# PWR_PROT.net
KiCad netlist of a schematic drawn in Altium Designer
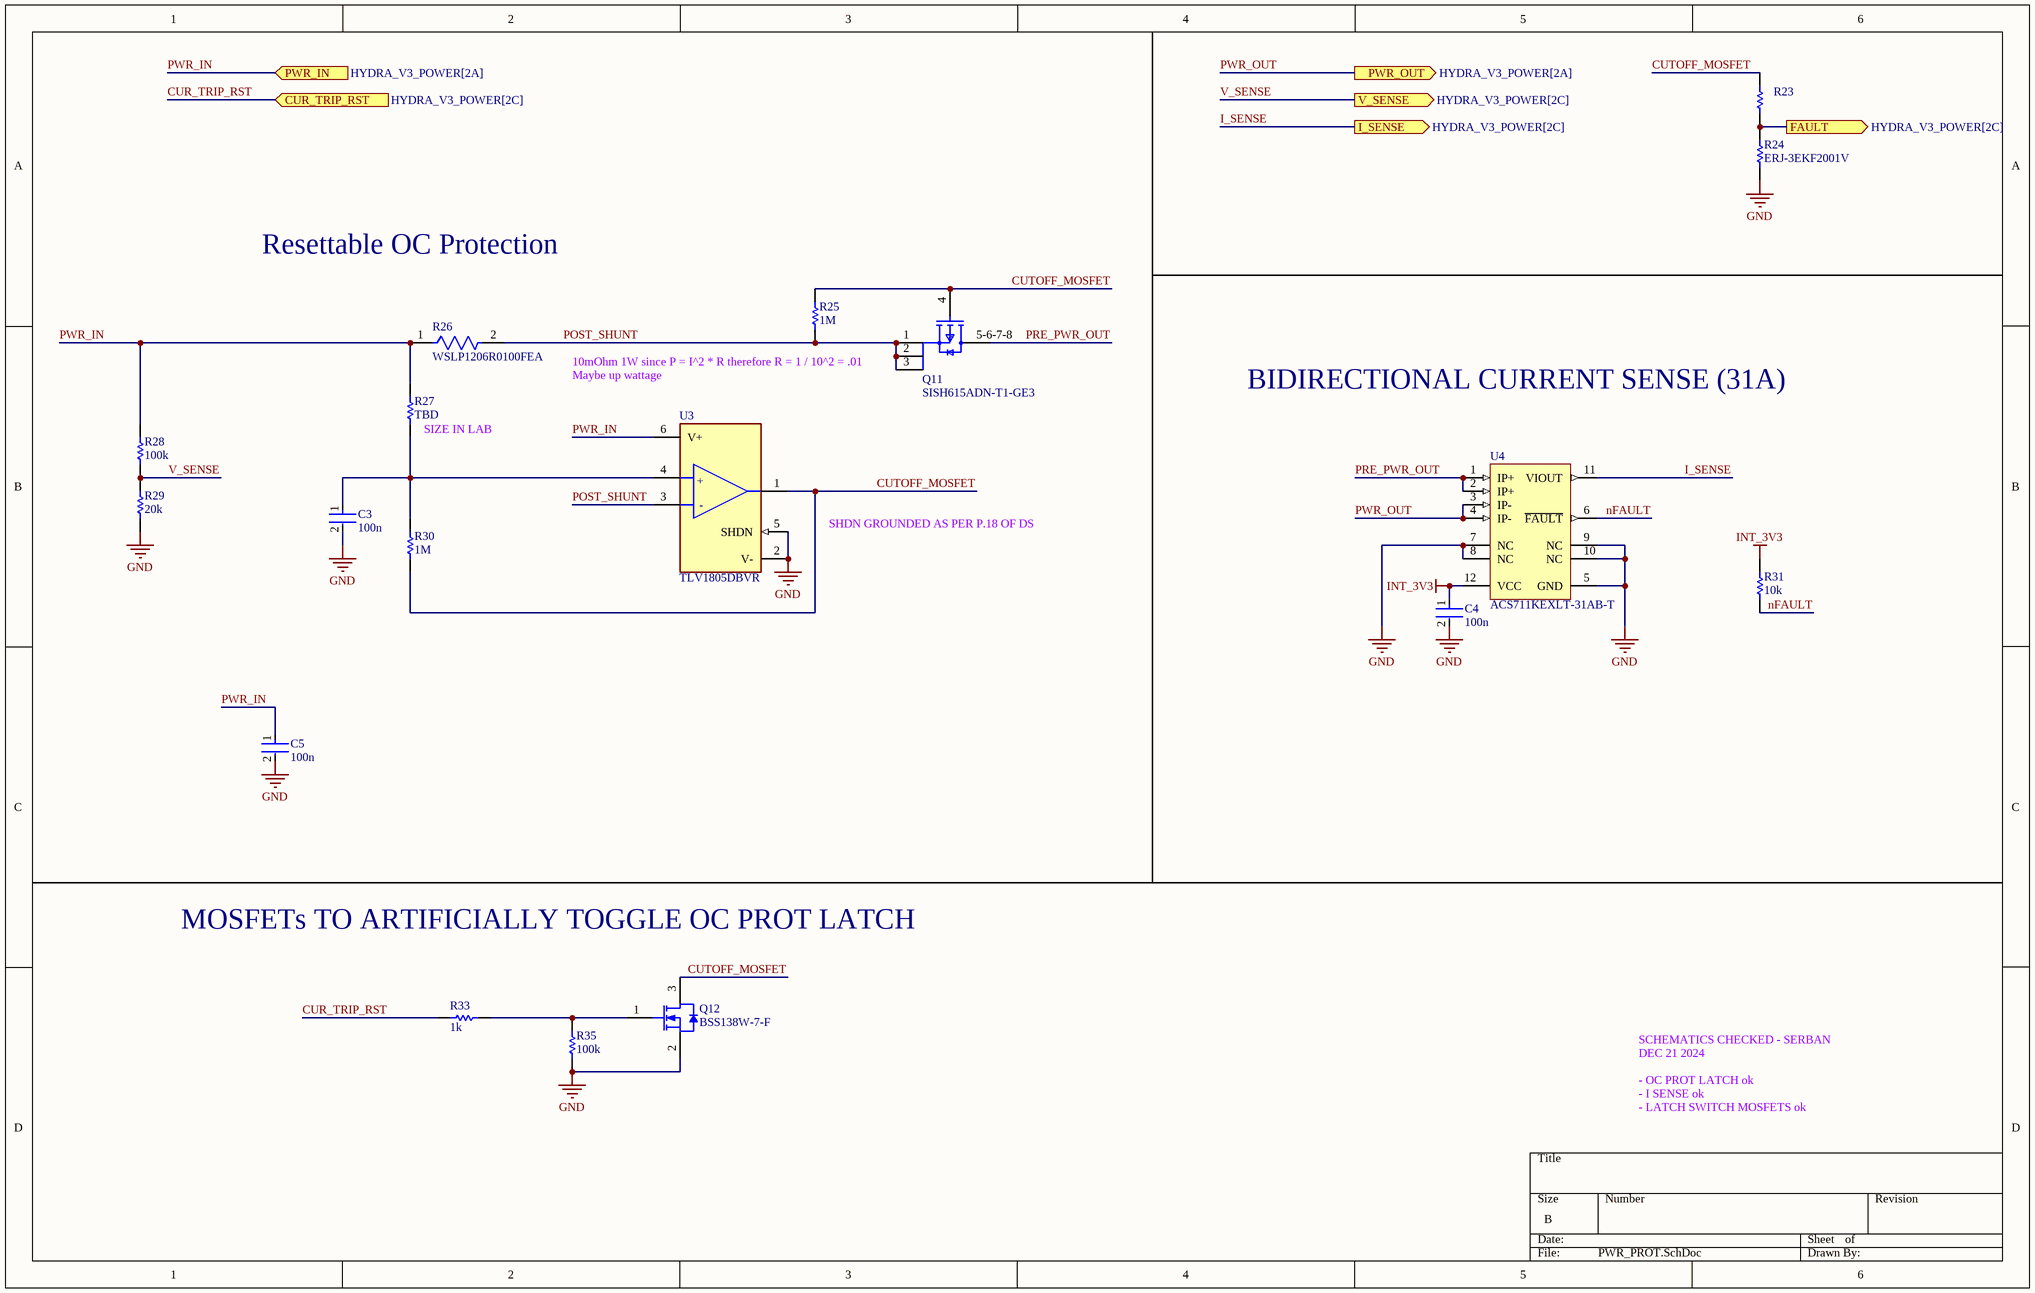
[diagram p0: PWR_PROT.SchDoc]

(export (version "E")
  (design (tool "Eeschema 10.0.6"))
  (components
    (comp (ref "C3")
      (value "100n")
      (footprint "FP-0402-L_1_0_0_05-W_0_5-IPC_A")
      (description "LARGE PADS, 0402 CAP, CHANGE COMMENT TO MATCH REAL P/N")
      (libsource (lib "Space Concordia") (part "b4654b650e69147ec39a6b967a45e02"))
    )
    (comp (ref "C4")
      (value "100n")
      (footprint "FP-0402-L_1_0_0_05-W_0_5-IPC_A")
      (description "LARGE PADS, 0402 CAP, CHANGE COMMENT TO MATCH REAL P/N")
      (libsource (lib "Space Concordia") (part "b4654b650e69147ec39a6b967a45e02"))
    )
    (comp (ref "C5")
      (value "100n")
      (footprint "FP-0402-L_1_0_0_05-W_0_5-IPC_A")
      (description "LARGE PADS, 0402 CAP, CHANGE COMMENT TO MATCH REAL P/N")
      (libsource (lib "Space Concordia") (part "b4654b650e69147ec39a6b967a45e02"))
    )
    (comp (ref "Q11")
      (value "SISH615ADN-T1-GE3")
      (footprint "SISH615ADN-T1-GE3-Footprint-1")
      (description "Trans MOSFET P-CH 20V 22.1A 8-Pin PowerPAK 1212 EP T/R")
      (libsource (lib "Space Concordia") (part "CMP-013-00036-4"))
    )
    (comp (ref "Q12")
      (value "BSS138W-7-F")
      (footprint "DIOD-SOT323-3_V")
      (fields (field (name "MANUFACTURER") "DiodesIncorporated"))
      (libsource (lib "Altium Content Vault") (part "NEMOS-GSD-3"))
    )
    (comp (ref "R23")
      (value "ERJ3EKF1002V")
      (footprint "RESC1609X55X30LL15T15")
      (description "Chip Resistor, 10 KOhm, +/- 1%, 0.1 W, -55 to 155 degC, 0603 (1608 Metric), RoHS, Tape and Reel")
      (fields (field (name "TOLERANCE") "1%") (field (name "MANUFACTURER") "Panasonic"))
      (libsource (lib "Altium Content Vault") (part "RES-2"))
    )
    (comp (ref "R24")
      (value "ERJ-3EKF2001V")
      (footprint "RESC1608X55X30ML15T15")
      (fields (field (name "MANUFACTURER") "Panasonic"))
      (libsource (lib "Altium Content Vault") (part "RES"))
    )
    (comp (ref "R25")
      (value "1M")
      (footprint "R0603B")
      (description "Resistor")
      (libsource (lib "Space Concordia") (part "Resistor"))
    )
    (comp (ref "R26")
      (value "WSLP1206R0100FEA")
      (footprint "FP-WSLP1206-FP_1_65x1_93x-MFG")
      (description "RES 0.01 OHM 1% 1W 1206")
      (fields (field (name "TOLERANCE") "1%"))
      (libsource (lib "Altium Content Vault") (part "1029c3af85768c4190bb7ad29bc67b5"))
    )
    (comp (ref "R27")
      (value "TBD")
      (footprint "R0603B")
      (description "Resistor")
      (libsource (lib "Space Concordia") (part "Resistor"))
    )
    (comp (ref "R28")
      (value "100k")
      (footprint "R0603B")
      (description "Resistor")
      (libsource (lib "Space Concordia") (part "Resistor"))
    )
    (comp (ref "R29")
      (value "20k")
      (footprint "R0603B")
      (description "Resistor")
      (libsource (lib "Space Concordia") (part "Resistor"))
    )
    (comp (ref "R30")
      (value "1M")
      (footprint "R0603B")
      (description "Resistor")
      (libsource (lib "Space Concordia") (part "Resistor"))
    )
    (comp (ref "R31")
      (value "10k")
      (footprint "R0603B")
      (description "Resistor")
      (libsource (lib "Space Concordia") (part "Resistor"))
    )
    (comp (ref "R33")
      (value "1k")
      (footprint "R0603B")
      (description "Resistor")
      (libsource (lib "Space Concordia") (part "Resistor"))
    )
    (comp (ref "R35")
      (value "100k")
      (footprint "R0603B")
      (description "Resistor")
      (libsource (lib "Space Concordia") (part "Resistor"))
    )
    (comp (ref "U3")
      (value "TLV1805DBVR")
      (footprint "FP-DBV0006A-IPC_C")
      (description "40V, RAIL-TO-RAIL INPUT, PUSH-PU")
      (libsource (lib "Altium Content Vault") (part "c7aa3bc3dbf0dc8b0b0354779bd1228"))
    )
    (comp (ref "U4")
      (value "ACS711KEXLT-31AB-T")
      (footprint "ALEG-EX-12_V")
      (libsource (lib "Altium Content Vault") (part "ALEG-ACS711-QFN-12"))
    )
  )
  (nets
    (net (code "1") (name "/CUR_TRIP_RST") (class "Default")
      (node (ref "R33") (pin "2") (pinfunction "2_2") (pintype "passive"))
    )
    (net (code "2") (name "/CUTOFF_MOSFET") (class "Default")
      (node (ref "Q11") (pin "4") (pinfunction "G_4") (pintype "passive"))
      (node (ref "Q12") (pin "3") (pinfunction "D_3") (pintype "passive"))
      (node (ref "R23") (pin "1") (pinfunction "1_1") (pintype "passive"))
      (node (ref "R25") (pin "2") (pinfunction "2_2") (pintype "passive"))
      (node (ref "R30") (pin "1") (pinfunction "1_1") (pintype "passive"))
      (node (ref "U3") (pin "1") (pinfunction "OUT_1") (pintype "passive"))
    )
    (net (code "3") (name "/FAULT") (class "Default")
      (node (ref "R23") (pin "2") (pinfunction "2_2") (pintype "passive"))
      (node (ref "R24") (pin "2") (pinfunction "2_2") (pintype "passive"))
    )
    (net (code "4") (name "/I_SENSE") (class "Default")
      (node (ref "U4") (pin "11") (pinfunction "VIOUT_11") (pintype "output"))
    )
    (net (code "5") (name "/POST_SHUNT") (class "Default")
      (node (ref "Q11") (pin "1") (pinfunction "S_1") (pintype "passive"))
      (node (ref "Q11") (pin "2") (pinfunction "S_2") (pintype "passive"))
      (node (ref "Q11") (pin "3") (pinfunction "S_3") (pintype "passive"))
      (node (ref "R25") (pin "1") (pinfunction "1_1") (pintype "passive"))
      (node (ref "R26") (pin "2") (pinfunction "2_2") (pintype "passive"))
      (node (ref "U3") (pin "3") (pinfunction "-IN_3") (pintype "tri_state"))
    )
    (net (code "6") (name "/PRE_PWR_OUT") (class "Default")
      (node (ref "Q11") (pin "5-6-7-8") (pinfunction "D_5-6-7-8") (pintype "passive"))
      (node (ref "U4") (pin "1") (pinfunction "IP+_1") (pintype "input"))
      (node (ref "U4") (pin "2") (pinfunction "IP+_2") (pintype "input"))
    )
    (net (code "7") (name "/PWR_IN") (class "Default")
      (node (ref "C5") (pin "1") (pinfunction "1_1") (pintype "passive"))
      (node (ref "R26") (pin "1") (pinfunction "1_1") (pintype "passive"))
      (node (ref "R27") (pin "2") (pinfunction "2_2") (pintype "passive"))
      (node (ref "R28") (pin "2") (pinfunction "2_2") (pintype "passive"))
      (node (ref "U3") (pin "6") (pinfunction "V+_6") (pintype "power_in"))
    )
    (net (code "8") (name "/PWR_OUT") (class "Default")
      (node (ref "U4") (pin "3") (pinfunction "IP-_3") (pintype "input"))
      (node (ref "U4") (pin "4") (pinfunction "IP-_4") (pintype "input"))
    )
    (net (code "9") (name "/V_SENSE") (class "Default")
      (node (ref "R28") (pin "1") (pinfunction "1_1") (pintype "passive"))
      (node (ref "R29") (pin "2") (pinfunction "2_2") (pintype "passive"))
    )
    (net (code "10") (name "/nFAULT") (class "Default")
      (node (ref "R31") (pin "1") (pinfunction "1_1") (pintype "passive"))
      (node (ref "U4") (pin "6") (pinfunction "~{FAULT}_6") (pintype "output"))
    )
    (net (code "11") (name "GND") (class "Default")
      (node (ref "C3") (pin "2") (pinfunction "2_2") (pintype "passive"))
      (node (ref "C4") (pin "2") (pinfunction "2_2") (pintype "passive"))
      (node (ref "C5") (pin "2") (pinfunction "2_2") (pintype "passive"))
      (node (ref "Q12") (pin "2") (pinfunction "S_2") (pintype "passive"))
      (node (ref "R24") (pin "1") (pinfunction "1_1") (pintype "passive"))
      (node (ref "R29") (pin "1") (pinfunction "1_1") (pintype "passive"))
      (node (ref "R35") (pin "1") (pinfunction "1_1") (pintype "passive"))
      (node (ref "U3") (pin "2") (pinfunction "V-_2") (pintype "power_in"))
      (node (ref "U3") (pin "5") (pinfunction "SHDN_5") (pintype "input"))
      (node (ref "U4") (pin "10") (pinfunction "NC_10") (pintype "passive"))
      (node (ref "U4") (pin "5") (pinfunction "GND_5") (pintype "power_in"))
      (node (ref "U4") (pin "7") (pinfunction "NC_7") (pintype "passive"))
      (node (ref "U4") (pin "8") (pinfunction "NC_8") (pintype "passive"))
      (node (ref "U4") (pin "9") (pinfunction "NC_9") (pintype "passive"))
    )
    (net (code "12") (name "INT_3V3") (class "Default")
      (node (ref "C4") (pin "1") (pinfunction "1_1") (pintype "passive"))
      (node (ref "R31") (pin "2") (pinfunction "2_2") (pintype "passive"))
      (node (ref "U4") (pin "12") (pinfunction "VCC_12") (pintype "power_in"))
    )
    (net (code "13") (name "Net-(Q12-G)") (class "Default")
      (node (ref "Q12") (pin "1") (pinfunction "G_1") (pintype "passive"))
      (node (ref "R33") (pin "1") (pinfunction "1_1") (pintype "passive"))
      (node (ref "R35") (pin "2") (pinfunction "2_2") (pintype "passive"))
    )
    (net (code "14") (name "Net-(U3-+IN)") (class "Default")
      (node (ref "C3") (pin "1") (pinfunction "1_1") (pintype "passive"))
      (node (ref "R27") (pin "1") (pinfunction "1_1") (pintype "passive"))
      (node (ref "R30") (pin "2") (pinfunction "2_2") (pintype "passive"))
      (node (ref "U3") (pin "4") (pinfunction "+IN_4") (pintype "tri_state"))
    )
  )
)
